# Eth.net
KiCad netlist of a schematic drawn in Altium Designer
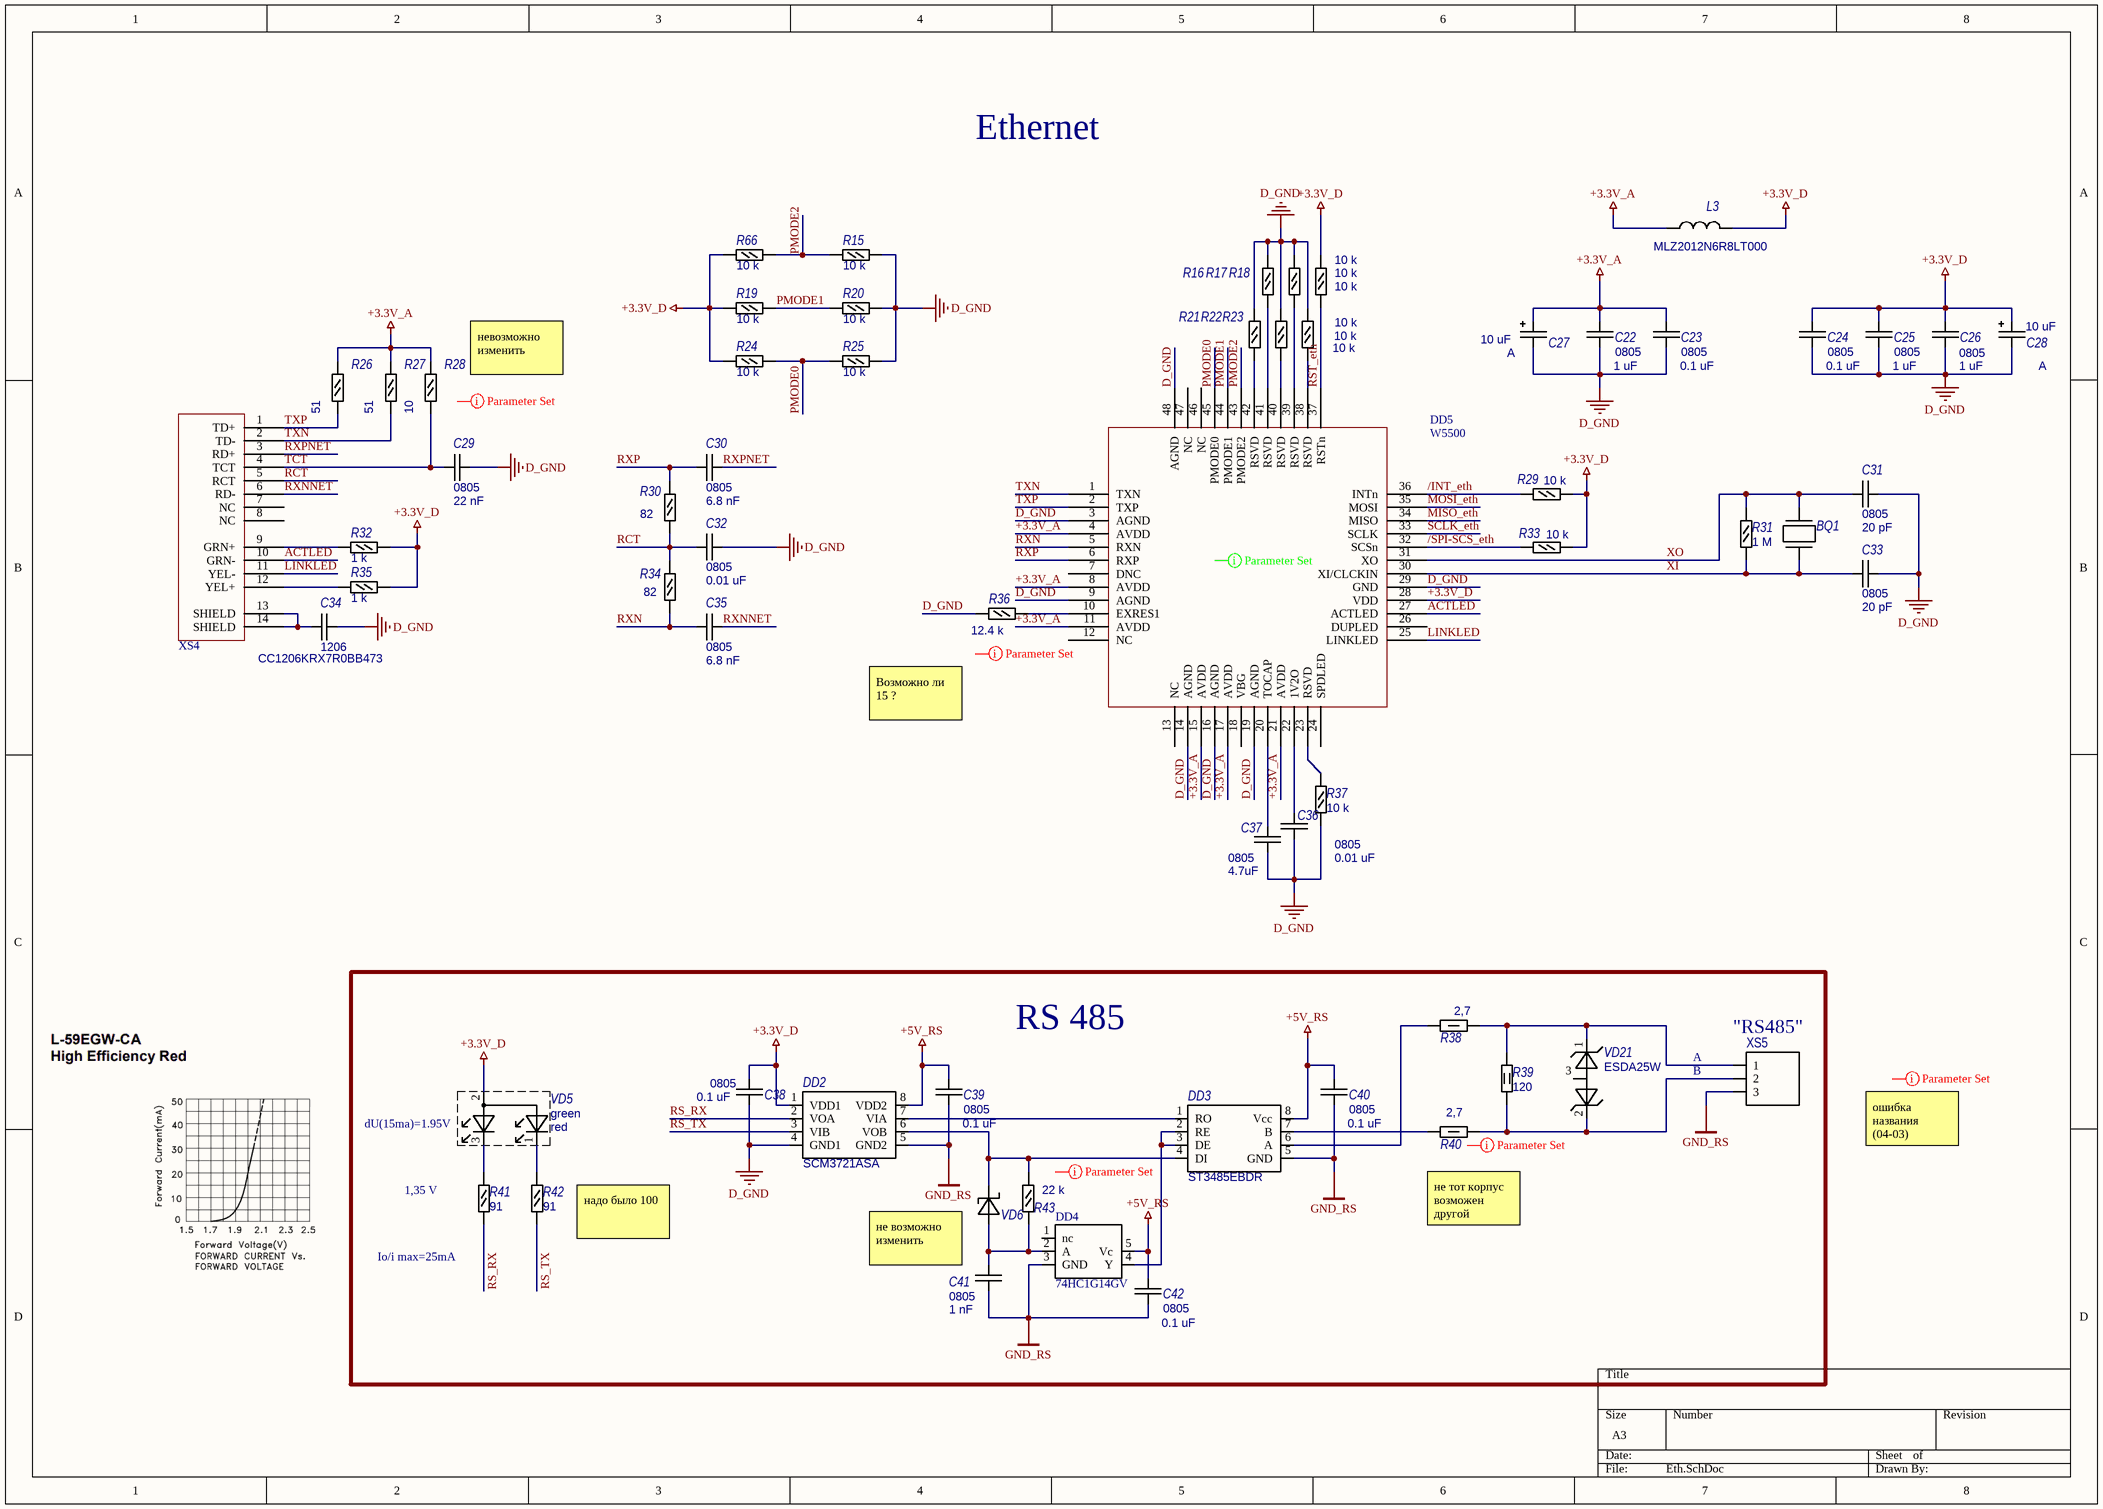
[diagram p0: Eth.SchDoc]

(export (version "E")
  (design (tool "Eeschema 10.0.6"))
  (components
    (comp (ref "BQ1") (value "~") (footprint "Xtal_HC49S") (libsource (lib "Privod_A_K") (part "Xtal")))
    (comp (ref "C22")
      (value "0805")
      (footprint "CAP_0805_(2x1.25x1.3)")
      (description "Керамика")
      (fields (field (name "НОМИНАЛ") "1 uF"))
      (libsource (lib "Privod_A_K") (part "C_0805"))
    )
    (comp (ref "C23")
      (value "0805")
      (footprint "CAP_0805_(2x1.25x1.3)")
      (description "Керамика")
      (fields (field (name "НОМИНАЛ") "0.1 uF"))
      (libsource (lib "Privod_A_K") (part "C_0805"))
    )
    (comp (ref "C24")
      (value "0805")
      (footprint "CAP_0805_(2x1.25x1.3)")
      (description "Керамика")
      (fields (field (name "НОМИНАЛ") "0.1 uF"))
      (libsource (lib "Privod_A_K") (part "C_0805"))
    )
    (comp (ref "C25")
      (value "0805")
      (footprint "CAP_0805_(2x1.25x1.3)")
      (description "Керамика")
      (fields (field (name "НОМИНАЛ") "1 uF"))
      (libsource (lib "Privod_A_K") (part "C_0805"))
    )
    (comp (ref "C26")
      (value "0805")
      (footprint "CAP_0805_(2x1.25x1.3)")
      (description "Керамика")
      (fields (field (name "НОМИНАЛ") "1 uF"))
      (libsource (lib "Privod_A_K") (part "C_0805"))
    )
    (comp (ref "C27")
      (value "TAN_A")
      (footprint "CAP_TAN_A")
      (description "Capacitor")
      (fields (field (name "КОРПУС") "A") (field (name "НОМИНАЛ") "10 uF"))
      (libsource (lib "Privod_A_K") (part "C+_TAN_A"))
    )
    (comp (ref "C28")
      (value "TAN_A")
      (footprint "CAP_TAN_A")
      (description "Capacitor")
      (fields (field (name "КОРПУС") "A") (field (name "НОМИНАЛ") "10 uF"))
      (libsource (lib "Privod_A_K") (part "C+_TAN_A"))
    )
    (comp (ref "C29")
      (value "0805")
      (footprint "CAP_0805_(2x1.25x1.3)")
      (description "Керамика")
      (fields (field (name "НОМИНАЛ") "22 nF"))
      (libsource (lib "Privod_A_K") (part "C_0805"))
    )
    (comp (ref "C30")
      (value "0805")
      (footprint "CAP_0805_(2x1.25x1.3)")
      (description "Керамика")
      (fields (field (name "НОМИНАЛ") "6.8 nF"))
      (libsource (lib "Privod_A_K") (part "C_0805"))
    )
    (comp (ref "C31")
      (value "0805")
      (footprint "CAP_0805_(2x1.25x1.3)")
      (description "Керамика")
      (fields (field (name "НОМИНАЛ") "20 pF"))
      (libsource (lib "Privod_A_K") (part "C_0805"))
    )
    (comp (ref "C32")
      (value "0805")
      (footprint "CAP_0805_(2x1.25x1.3)")
      (description "Керамика")
      (fields (field (name "НОМИНАЛ") "0.01 uF"))
      (libsource (lib "Privod_A_K") (part "C_0805"))
    )
    (comp (ref "C33")
      (value "0805")
      (footprint "CAP_0805_(2x1.25x1.3)")
      (description "Керамика")
      (fields (field (name "НОМИНАЛ") "20 pF"))
      (libsource (lib "Privod_A_K") (part "C_0805"))
    )
    (comp (ref "C34")
      (value "1206")
      (footprint "CAP_1206_(3.2x1.6x1.5)")
      (description "Керамика")
      (fields (field (name "НАИМЕНОВАНИЕ") "CC1206KRX7R0BB473"))
      (libsource (lib "Privod_A_K") (part "C_1206"))
    )
    (comp (ref "C35")
      (value "0805")
      (footprint "CAP_0805_(2x1.25x1.3)")
      (description "Керамика")
      (fields (field (name "НОМИНАЛ") "6.8 nF"))
      (libsource (lib "Privod_A_K") (part "C_0805"))
    )
    (comp (ref "C36")
      (value "0805")
      (footprint "CAP_0805_(2x1.25x1.3)")
      (description "Керамика")
      (fields (field (name "НОМИНАЛ") "0.01 uF"))
      (libsource (lib "Privod_A_K") (part "C_0805"))
    )
    (comp (ref "C37")
      (value "0805")
      (footprint "CAP_0805_(2x1.25x1.3)")
      (description "Керамика")
      (fields (field (name "НОМИНАЛ") "4.7uF"))
      (libsource (lib "Privod_A_K") (part "C_0805"))
    )
    (comp (ref "C38")
      (value "0805")
      (footprint "CAP_0805_(2x1.25x1.3)")
      (description "Керамика")
      (fields (field (name "НОМИНАЛ") "0.1 uF"))
      (libsource (lib "Privod_A_K") (part "C_0805"))
    )
    (comp (ref "C39")
      (value "0805")
      (footprint "CAP_0805_(2x1.25x1.3)")
      (description "Керамика")
      (fields (field (name "НОМИНАЛ") "0.1 uF"))
      (libsource (lib "Privod_A_K") (part "C_0805"))
    )
    (comp (ref "C40")
      (value "0805")
      (footprint "CAP_0805_(2x1.25x1.3)")
      (description "Керамика")
      (fields (field (name "НОМИНАЛ") "0.1 uF"))
      (libsource (lib "Privod_A_K") (part "C_0805"))
    )
    (comp (ref "C41")
      (value "0805")
      (footprint "CAP_0805_(2x1.25x1.3)")
      (description "Керамика")
      (fields (field (name "НОМИНАЛ") "1 nF"))
      (libsource (lib "Privod_A_K") (part "C_0805"))
    )
    (comp (ref "C42")
      (value "0805")
      (footprint "CAP_0805_(2x1.25x1.3)")
      (description "Керамика")
      (fields (field (name "НОМИНАЛ") "0.1 uF"))
      (libsource (lib "Privod_A_K") (part "C_0805"))
    )
    (comp (ref "DD2")
      (value "SCM3721ASA")
      (footprint "SOP-8")
      (description "Dual-ChannelDigital Isolators")
      (libsource (lib "Privod_A_K") (part "DD_SCM3721ASA"))
    )
    (comp (ref "DD3")
      (value "ST3485EBDR")
      (footprint "SO-8_(0.15')")
      (description "RS485/422 Приемопередатчик интерфейса")
      (libsource (lib "Privod_A_K") (part "DD_ST3485EBDR"))
    )
    (comp (ref "DD4")
      (value "74HC1G14GV")
      (footprint "sot-23-5")
      (description "1 канал инвертирующ триггер шмитта")
      (libsource (lib "Privod_A_K") (part "DD_74HC1G14GV"))
    )
    (comp (ref "DD5") (value "W5500") (footprint "LQFP_48") (libsource (lib "Privod_A_K") (part "DD_W5500")))
    (comp (ref "L3")
      (value "PBY201209T-601Y-N")
      (footprint "L_0805")
      (description "L")
      (fields (field (name "НАИМЕНОВАНИЕ") "MLZ2012N6R8LT000"))
      (libsource (lib "Privod_A_K") (part "L_PBY201209T-601Y-N"))
    )
    (comp (ref "R15")
      (value "0805")
      (footprint "RES_0805_(2x1.2x0.45)_0.125Вт")
      (description "Resistor")
      (fields (field (name "НОМИНАЛ") "10 k"))
      (libsource (lib "") (part "R_0805_1"))
    )
    (comp (ref "R16")
      (value "0805")
      (footprint "RES_0805_(2x1.2x0.45)_0.125Вт")
      (description "Resistor")
      (fields (field (name "НОМИНАЛ") "10 k"))
      (libsource (lib "Privod_A_K") (part "R_0805"))
    )
    (comp (ref "R17")
      (value "0805")
      (footprint "RES_0805_(2x1.2x0.45)_0.125Вт")
      (description "Resistor")
      (fields (field (name "НОМИНАЛ") "10 k"))
      (libsource (lib "Privod_A_K") (part "R_0805"))
    )
    (comp (ref "R18")
      (value "0805")
      (footprint "RES_0805_(2x1.2x0.45)_0.125Вт")
      (description "Resistor")
      (fields (field (name "НОМИНАЛ") "10 k"))
      (libsource (lib "Privod_A_K") (part "R_0805"))
    )
    (comp (ref "R19")
      (value "0805")
      (footprint "RES_0805_(2x1.2x0.45)_0.125Вт")
      (description "Resistor")
      (fields (field (name "НОМИНАЛ") "10 k"))
      (libsource (lib "") (part "R_0805_1"))
    )
    (comp (ref "R20")
      (value "0805")
      (footprint "RES_0805_(2x1.2x0.45)_0.125Вт")
      (description "Resistor")
      (fields (field (name "НОМИНАЛ") "10 k"))
      (libsource (lib "") (part "R_0805_1"))
    )
    (comp (ref "R21")
      (value "0805")
      (footprint "RES_0805_(2x1.2x0.45)_0.125Вт")
      (description "Resistor")
      (fields (field (name "НОМИНАЛ") "10 k"))
      (libsource (lib "Privod_A_K") (part "R_0805"))
    )
    (comp (ref "R22")
      (value "0805")
      (footprint "RES_0805_(2x1.2x0.45)_0.125Вт")
      (description "Resistor")
      (fields (field (name "НОМИНАЛ") "10 k"))
      (libsource (lib "Privod_A_K") (part "R_0805"))
    )
    (comp (ref "R23")
      (value "0805")
      (footprint "RES_0805_(2x1.2x0.45)_0.125Вт")
      (description "Resistor")
      (fields (field (name "НОМИНАЛ") "10 k"))
      (libsource (lib "Privod_A_K") (part "R_0805"))
    )
    (comp (ref "R24")
      (value "0805")
      (footprint "RES_0805_(2x1.2x0.45)_0.125Вт")
      (description "Resistor")
      (fields (field (name "НОМИНАЛ") "10 k"))
      (libsource (lib "") (part "R_0805_1"))
    )
    (comp (ref "R25")
      (value "0805")
      (footprint "RES_0805_(2x1.2x0.45)_0.125Вт")
      (description "Resistor")
      (fields (field (name "НОМИНАЛ") "10 k"))
      (libsource (lib "") (part "R_0805_1"))
    )
    (comp (ref "R26")
      (value "0805")
      (footprint "RES_0805_(2x1.2x0.45)_0.125Вт")
      (description "Resistor")
      (fields (field (name "НОМИНАЛ") "51"))
      (libsource (lib "Privod_A_K") (part "R_0805"))
    )
    (comp (ref "R27")
      (value "0805")
      (footprint "RES_0805_(2x1.2x0.45)_0.125Вт")
      (description "Resistor")
      (fields (field (name "НОМИНАЛ") "51"))
      (libsource (lib "Privod_A_K") (part "R_0805"))
    )
    (comp (ref "R28")
      (value "0805")
      (footprint "RES_0805_(2x1.2x0.45)_0.125Вт")
      (description "Resistor")
      (fields (field (name "НОМИНАЛ") "10"))
      (libsource (lib "Privod_A_K") (part "R_0805"))
    )
    (comp (ref "R29")
      (value "0805")
      (footprint "RES_0805_(2x1.2x0.45)_0.125Вт")
      (description "Resistor")
      (fields (field (name "НОМИНАЛ") "10 k"))
      (libsource (lib "") (part "R_0805_1"))
    )
    (comp (ref "R30")
      (value "0805")
      (footprint "RES_0805_(2x1.2x0.45)_0.125Вт")
      (description "Resistor")
      (fields (field (name "НОМИНАЛ") "82"))
      (libsource (lib "Privod_A_K") (part "R_0805"))
    )
    (comp (ref "R31")
      (value "0805")
      (footprint "RES_0805_(2x1.2x0.45)_0.125Вт")
      (description "Resistor")
      (fields (field (name "НОМИНАЛ") "1 M"))
      (libsource (lib "Privod_A_K") (part "R_0805"))
    )
    (comp (ref "R32")
      (value "0805")
      (footprint "RES_0805_(2x1.2x0.45)_0.125Вт")
      (description "Resistor")
      (fields (field (name "НОМИНАЛ") "1 k"))
      (libsource (lib "") (part "R_0805_1"))
    )
    (comp (ref "R33")
      (value "0805")
      (footprint "RES_0805_(2x1.2x0.45)_0.125Вт")
      (description "Resistor")
      (fields (field (name "НОМИНАЛ") "10 k"))
      (libsource (lib "") (part "R_0805_1"))
    )
    (comp (ref "R34")
      (value "0805")
      (footprint "RES_0805_(2x1.2x0.45)_0.125Вт")
      (description "Resistor")
      (fields (field (name "НОМИНАЛ") "82"))
      (libsource (lib "Privod_A_K") (part "R_0805"))
    )
    (comp (ref "R35")
      (value "0805")
      (footprint "RES_0805_(2x1.2x0.45)_0.125Вт")
      (description "Resistor")
      (fields (field (name "НОМИНАЛ") "1 k"))
      (libsource (lib "") (part "R_0805_1"))
    )
    (comp (ref "R36")
      (value "0805")
      (footprint "RES_0805_(2x1.2x0.45)_0.125Вт")
      (description "Resistor")
      (fields (field (name "НОМИНАЛ") "12.4 k"))
      (libsource (lib "") (part "R_0805_1"))
    )
    (comp (ref "R37")
      (value "0805")
      (footprint "RES_0805_(2x1.2x0.45)_0.125Вт")
      (description "Resistor")
      (fields (field (name "НОМИНАЛ") "10 k"))
      (libsource (lib "Privod_A_K") (part "R_0805"))
    )
    (comp (ref "R38")
      (value "1210")
      (footprint "RES_1210_(3.2x2.5x0.55)_0.5Вт")
      (description "Resistor")
      (fields (field (name "НОМИНАЛ") "2,7"))
      (libsource (lib "Privod_A_K") (part "R_1210"))
    )
    (comp (ref "R39")
      (value "2512")
      (footprint "RES_2512_(6.3x3.1x0.6)_2Вт")
      (description "Токочувствительные резисторы – для поверхностного монтажа 2watts 2512")
      (fields (field (name "НОМИНАЛ") "120"))
      (libsource (lib "Privod_A_K") (part "R_2512"))
    )
    (comp (ref "R40")
      (value "1210")
      (footprint "RES_1210_(3.2x2.5x0.55)_0.5Вт")
      (description "Resistor")
      (fields (field (name "НОМИНАЛ") "2,7"))
      (libsource (lib "Privod_A_K") (part "R_1210"))
    )
    (comp (ref "R41")
      (value "0805")
      (footprint "RES_0805_(2x1.2x0.45)_0.125Вт")
      (description "Resistor")
      (fields (field (name "НОМИНАЛ") "91"))
      (libsource (lib "Privod_A_K") (part "R_0805"))
    )
    (comp (ref "R42")
      (value "0805")
      (footprint "RES_0805_(2x1.2x0.45)_0.125Вт")
      (description "Resistor")
      (fields (field (name "НОМИНАЛ") "91"))
      (libsource (lib "Privod_A_K") (part "R_0805"))
    )
    (comp (ref "R43")
      (value "0805")
      (footprint "RES_0805_(2x1.2x0.45)_0.125Вт")
      (description "Resistor")
      (fields (field (name "НОМИНАЛ") "22 k"))
      (libsource (lib "") (part "R_0805_2"))
    )
    (comp (ref "R66")
      (value "0805")
      (footprint "RES_0805_(2x1.2x0.45)_0.125Вт")
      (description "Resistor")
      (fields (field (name "НОМИНАЛ") "10 k"))
      (libsource (lib "") (part "R_0805_1"))
    )
    (comp (ref "VD5")
      (value "VD_Ledx2_dip")
      (footprint "VD_LEDsx2")
      (fields (field (name "ТИП") "green") (field (name "ПРИМЕЧАНИЯ") "red"))
      (libsource (lib "Privod_A_K") (part "VD_Ledx2_dip"))
    )
    (comp (ref "VD6")
      (value "VD_SH_SMA")
      (footprint "VD_SMA_(Do-214AC)")
      (description "Sh_Diode")
      (libsource (lib "Privod_A_K") (part "VD_SH_SMA"))
    )
    (comp (ref "VD21")
      (value "ESDA25W")
      (footprint "SOT-323-3L")
      (description "Защитный биполярный диод")
      (libsource (lib "Privod_A_K") (part "VD_ESDA25W"))
    )
    (comp (ref "XS4")
      (value "XS_HR911105A")
      (footprint "XS_HR911105A(RJ45)")
      (description "RJ45")
      (libsource (lib "Privod_A_K") (part "XS_HR911105A"))
    )
    (comp (ref "XS5")
      (value "XS_3_pin_3.8mm")
      (footprint "XS_3_Pin _3.8mm")
      (libsource (lib "Privod_A_K") (part "XS_3_pin_3.8mm"))
    )
  )
  (nets
    (net (code "1") (name "+3.3V_A") (class "Default")
      (node (ref "C22") (pin "2") (pinfunction "2_2") (pintype "passive"))
      (node (ref "C23") (pin "2") (pinfunction "2_2") (pintype "passive"))
      (node (ref "C27") (pin "1") (pinfunction "1_1") (pintype "passive"))
      (node (ref "DD5") (pin "11") (pinfunction "AVDD_11") (pintype "passive"))
      (node (ref "DD5") (pin "15") (pinfunction "AVDD_15") (pintype "passive"))
      (node (ref "DD5") (pin "17") (pinfunction "AVDD_17") (pintype "passive"))
      (node (ref "DD5") (pin "21") (pinfunction "AVDD_21") (pintype "passive"))
      (node (ref "DD5") (pin "4") (pinfunction "AVDD_4") (pintype "passive"))
      (node (ref "DD5") (pin "8") (pinfunction "AVDD_8") (pintype "passive"))
      (node (ref "L3") (pin "1") (pinfunction "1_1") (pintype "passive"))
      (node (ref "R26") (pin "2") (pinfunction "2_2") (pintype "passive"))
      (node (ref "R27") (pin "2") (pinfunction "2_2") (pintype "passive"))
      (node (ref "R28") (pin "2") (pinfunction "2_2") (pintype "passive"))
    )
    (net (code "2") (name "+3.3V_D") (class "Default")
      (node (ref "C24") (pin "2") (pinfunction "2_2") (pintype "passive"))
      (node (ref "C25") (pin "2") (pinfunction "2_2") (pintype "passive"))
      (node (ref "C26") (pin "2") (pinfunction "2_2") (pintype "passive"))
      (node (ref "C28") (pin "1") (pinfunction "1_1") (pintype "passive"))
      (node (ref "C38") (pin "2") (pinfunction "2_2") (pintype "passive"))
      (node (ref "DD2") (pin "1") (pinfunction "VDD1_1") (pintype "passive"))
      (node (ref "DD5") (pin "28") (pinfunction "VDD_28") (pintype "passive"))
      (node (ref "L3") (pin "2") (pinfunction "2_2") (pintype "passive"))
      (node (ref "R18") (pin "2") (pinfunction "2_2") (pintype "passive"))
      (node (ref "R19") (pin "1") (pinfunction "1_1") (pintype "passive"))
      (node (ref "R24") (pin "1") (pinfunction "1_1") (pintype "passive"))
      (node (ref "R29") (pin "2") (pinfunction "2_2") (pintype "passive"))
      (node (ref "R32") (pin "2") (pinfunction "2_2") (pintype "passive"))
      (node (ref "R33") (pin "2") (pinfunction "2_2") (pintype "passive"))
      (node (ref "R35") (pin "2") (pinfunction "2_2") (pintype "passive"))
      (node (ref "R66") (pin "1") (pinfunction "1_1") (pintype "passive"))
      (node (ref "VD5") (pin "2") (pinfunction "A_2") (pintype "passive"))
    )
    (net (code "3") (name "+5V_RS") (class "Default")
      (node (ref "C39") (pin "2") (pinfunction "2_2") (pintype "passive"))
      (node (ref "C40") (pin "2") (pinfunction "2_2") (pintype "passive"))
      (node (ref "C42") (pin "2") (pinfunction "2_2") (pintype "passive"))
      (node (ref "DD2") (pin "8") (pinfunction "VDD2_8") (pintype "passive"))
      (node (ref "DD3") (pin "8") (pinfunction "Vcc_8") (pintype "passive"))
      (node (ref "DD4") (pin "5") (pinfunction "Vc_5") (pintype "passive"))
    )
    (net (code "4") (name "/ACTLED") (class "Default")
      (node (ref "DD5") (pin "27") (pinfunction "ACTLED_27") (pintype "passive"))
      (node (ref "XS4") (pin "10") (pinfunction "GRN-_10") (pintype "passive"))
    )
    (net (code "5") (name "/LINKLED") (class "Default")
      (node (ref "DD5") (pin "25") (pinfunction "LINKLED_25") (pintype "passive"))
      (node (ref "XS4") (pin "11") (pinfunction "YEL-_11") (pintype "passive"))
    )
    (net (code "6") (name "/MISO_eth") (class "Default")
      (node (ref "DD5") (pin "34") (pinfunction "MISO_34") (pintype "passive"))
    )
    (net (code "7") (name "/MOSI_eth") (class "Default")
      (node (ref "DD5") (pin "35") (pinfunction "MOSI_35") (pintype "passive"))
    )
    (net (code "8") (name "/PMODE0") (class "Default")
      (node (ref "DD5") (pin "45") (pinfunction "PMODE0_45") (pintype "passive"))
      (node (ref "R24") (pin "2") (pinfunction "2_2") (pintype "passive"))
      (node (ref "R25") (pin "1") (pinfunction "1_1") (pintype "passive"))
    )
    (net (code "9") (name "/PMODE1") (class "Default")
      (node (ref "DD5") (pin "44") (pinfunction "PMODE1_44") (pintype "passive"))
      (node (ref "R19") (pin "2") (pinfunction "2_2") (pintype "passive"))
      (node (ref "R20") (pin "1") (pinfunction "1_1") (pintype "passive"))
    )
    (net (code "10") (name "/PMODE2") (class "Default")
      (node (ref "DD5") (pin "43") (pinfunction "PMODE2_43") (pintype "passive"))
      (node (ref "R15") (pin "1") (pinfunction "1_1") (pintype "passive"))
      (node (ref "R66") (pin "2") (pinfunction "2_2") (pintype "passive"))
    )
    (net (code "11") (name "/RCT") (class "Default")
      (node (ref "C32") (pin "2") (pinfunction "2_2") (pintype "passive"))
      (node (ref "R30") (pin "1") (pinfunction "1_1") (pintype "passive"))
      (node (ref "R34") (pin "2") (pinfunction "2_2") (pintype "passive"))
      (node (ref "XS4") (pin "5") (pinfunction "RCT_5") (pintype "passive"))
    )
    (net (code "12") (name "/RST_eth") (class "Default")
      (node (ref "DD5") (pin "37") (pinfunction "RSTn_37") (pintype "passive"))
      (node (ref "R18") (pin "1") (pinfunction "1_1") (pintype "passive"))
    )
    (net (code "13") (name "/RS_RX") (class "Default")
      (node (ref "DD2") (pin "2") (pinfunction "VOA_2") (pintype "passive"))
      (node (ref "R41") (pin "1") (pinfunction "1_1") (pintype "passive"))
    )
    (net (code "14") (name "/RS_TX") (class "Default")
      (node (ref "DD2") (pin "3") (pinfunction "VIB_3") (pintype "passive"))
      (node (ref "R42") (pin "1") (pinfunction "1_1") (pintype "passive"))
    )
    (net (code "15") (name "/RXN") (class "Default")
      (node (ref "C35") (pin "2") (pinfunction "2_2") (pintype "passive"))
      (node (ref "DD5") (pin "5") (pinfunction "RXN_5") (pintype "passive"))
      (node (ref "R34") (pin "1") (pinfunction "1_1") (pintype "passive"))
    )
    (net (code "16") (name "/RXNNET") (class "Default")
      (node (ref "C35") (pin "1") (pinfunction "1_1") (pintype "passive"))
      (node (ref "XS4") (pin "6") (pinfunction "RD-_6") (pintype "passive"))
    )
    (net (code "17") (name "/RXP") (class "Default")
      (node (ref "C30") (pin "2") (pinfunction "2_2") (pintype "passive"))
      (node (ref "DD5") (pin "6") (pinfunction "RXP_6") (pintype "passive"))
      (node (ref "R30") (pin "2") (pinfunction "2_2") (pintype "passive"))
    )
    (net (code "18") (name "/RXPNET") (class "Default")
      (node (ref "C30") (pin "1") (pinfunction "1_1") (pintype "passive"))
      (node (ref "XS4") (pin "3") (pinfunction "RD+_3") (pintype "passive"))
    )
    (net (code "19") (name "/SCLK_eth") (class "Default")
      (node (ref "DD5") (pin "33") (pinfunction "SCLK_33") (pintype "passive"))
    )
    (net (code "20") (name "/TCT") (class "Default")
      (node (ref "C29") (pin "2") (pinfunction "2_2") (pintype "passive"))
      (node (ref "R28") (pin "1") (pinfunction "1_1") (pintype "passive"))
      (node (ref "XS4") (pin "4") (pinfunction "TCT_4") (pintype "passive"))
    )
    (net (code "21") (name "/TXN") (class "Default")
      (node (ref "DD5") (pin "1") (pinfunction "TXN_1") (pintype "passive"))
      (node (ref "R27") (pin "1") (pinfunction "1_1") (pintype "passive"))
      (node (ref "XS4") (pin "2") (pinfunction "TD-_2") (pintype "passive"))
    )
    (net (code "22") (name "/TXP") (class "Default")
      (node (ref "DD5") (pin "2") (pinfunction "TXP_2") (pintype "passive"))
      (node (ref "R26") (pin "1") (pinfunction "1_1") (pintype "passive"))
      (node (ref "XS4") (pin "1") (pinfunction "TD+_1") (pintype "passive"))
    )
    (net (code "23") (name "/XI") (class "Default")
      (node (ref "BQ1") (pin "1") (pinfunction "1_1") (pintype "passive"))
      (node (ref "C33") (pin "2") (pinfunction "2_2") (pintype "passive"))
      (node (ref "DD5") (pin "30") (pinfunction "XI/CLCKIN_30") (pintype "passive"))
      (node (ref "R31") (pin "1") (pinfunction "1_1") (pintype "passive"))
    )
    (net (code "24") (name "/XO") (class "Default")
      (node (ref "BQ1") (pin "2") (pinfunction "2_2") (pintype "passive"))
      (node (ref "C31") (pin "2") (pinfunction "2_2") (pintype "passive"))
      (node (ref "DD5") (pin "31") (pinfunction "XO_31") (pintype "passive"))
      (node (ref "R31") (pin "2") (pinfunction "2_2") (pintype "passive"))
    )
    (net (code "25") (name "/{slash}INT_eth") (class "Default")
      (node (ref "DD5") (pin "36") (pinfunction "INTn_36") (pintype "passive"))
      (node (ref "R29") (pin "1") (pinfunction "1_1") (pintype "passive"))
    )
    (net (code "26") (name "/{slash}SPI-SCS_eth") (class "Default")
      (node (ref "DD5") (pin "32") (pinfunction "SCSn_32") (pintype "passive"))
      (node (ref "R33") (pin "1") (pinfunction "1_1") (pintype "passive"))
    )
    (net (code "27") (name "D_GND") (class "Default")
      (node (ref "C22") (pin "1") (pinfunction "1_1") (pintype "passive"))
      (node (ref "C23") (pin "1") (pinfunction "1_1") (pintype "passive"))
      (node (ref "C24") (pin "1") (pinfunction "1_1") (pintype "passive"))
      (node (ref "C25") (pin "1") (pinfunction "1_1") (pintype "passive"))
      (node (ref "C26") (pin "1") (pinfunction "1_1") (pintype "passive"))
      (node (ref "C27") (pin "2") (pinfunction "2_2") (pintype "passive"))
      (node (ref "C28") (pin "2") (pinfunction "2_2") (pintype "passive"))
      (node (ref "C29") (pin "1") (pinfunction "1_1") (pintype "passive"))
      (node (ref "C31") (pin "1") (pinfunction "1_1") (pintype "passive"))
      (node (ref "C32") (pin "1") (pinfunction "1_1") (pintype "passive"))
      (node (ref "C33") (pin "1") (pinfunction "1_1") (pintype "passive"))
      (node (ref "C34") (pin "2") (pinfunction "2_2") (pintype "passive"))
      (node (ref "C36") (pin "1") (pinfunction "1_1") (pintype "passive"))
      (node (ref "C37") (pin "1") (pinfunction "1_1") (pintype "passive"))
      (node (ref "C38") (pin "1") (pinfunction "1_1") (pintype "passive"))
      (node (ref "DD2") (pin "4") (pinfunction "GND1_4") (pintype "passive"))
      (node (ref "DD5") (pin "14") (pinfunction "AGND_14") (pintype "passive"))
      (node (ref "DD5") (pin "16") (pinfunction "AGND_16") (pintype "passive"))
      (node (ref "DD5") (pin "19") (pinfunction "AGND_19") (pintype "passive"))
      (node (ref "DD5") (pin "29") (pinfunction "GND_29") (pintype "passive"))
      (node (ref "DD5") (pin "3") (pinfunction "AGND_3") (pintype "passive"))
      (node (ref "DD5") (pin "48") (pinfunction "AGND_48") (pintype "passive"))
      (node (ref "DD5") (pin "9") (pinfunction "AGND_9") (pintype "passive"))
      (node (ref "R15") (pin "2") (pinfunction "2_2") (pintype "passive"))
      (node (ref "R16") (pin "2") (pinfunction "2_2") (pintype "passive"))
      (node (ref "R17") (pin "2") (pinfunction "2_2") (pintype "passive"))
      (node (ref "R20") (pin "2") (pinfunction "2_2") (pintype "passive"))
      (node (ref "R21") (pin "2") (pinfunction "2_2") (pintype "passive"))
      (node (ref "R22") (pin "2") (pinfunction "2_2") (pintype "passive"))
      (node (ref "R23") (pin "2") (pinfunction "2_2") (pintype "passive"))
      (node (ref "R25") (pin "2") (pinfunction "2_2") (pintype "passive"))
      (node (ref "R36") (pin "1") (pinfunction "1_1") (pintype "passive"))
      (node (ref "R37") (pin "1") (pinfunction "1_1") (pintype "passive"))
    )
    (net (code "28") (name "GND_RS") (class "Default")
      (node (ref "C39") (pin "1") (pinfunction "1_1") (pintype "passive"))
      (node (ref "C40") (pin "1") (pinfunction "1_1") (pintype "passive"))
      (node (ref "C41") (pin "1") (pinfunction "1_1") (pintype "passive"))
      (node (ref "C42") (pin "1") (pinfunction "1_1") (pintype "passive"))
      (node (ref "DD2") (pin "5") (pinfunction "GND2_5") (pintype "passive"))
      (node (ref "DD3") (pin "5") (pinfunction "GND_5") (pintype "passive"))
      (node (ref "DD4") (pin "3") (pinfunction "GND_3") (pintype "passive"))
      (node (ref "XS5") (pin "3") (pinfunction "3_3") (pintype "passive"))
    )
    (net (code "29") (name "Net-(C34-Pad1)") (class "Default")
      (node (ref "C34") (pin "1") (pinfunction "1_1") (pintype "passive"))
      (node (ref "XS4") (pin "13") (pinfunction "SHIELD_13") (pintype "passive"))
      (node (ref "XS4") (pin "14") (pinfunction "SHIELD_14") (pintype "passive"))
    )
    (net (code "30") (name "Net-(DD2-VIA)") (class "Default")
      (node (ref "DD2") (pin "7") (pinfunction "VIA_7") (pintype "passive"))
      (node (ref "DD3") (pin "1") (pinfunction "RO_1") (pintype "passive"))
    )
    (net (code "31") (name "Net-(DD2-VOB)") (class "Default")
      (node (ref "DD2") (pin "6") (pinfunction "VOB_6") (pintype "passive"))
      (node (ref "DD3") (pin "4") (pinfunction "DI_4") (pintype "passive"))
      (node (ref "R43") (pin "1") (pinfunction "1_1") (pintype "passive"))
      (node (ref "VD6") (pin "2") (pinfunction "K_2") (pintype "passive"))
    )
    (net (code "32") (name "Net-(DD3-A)") (class "Default")
      (node (ref "DD3") (pin "6") (pinfunction "A_6") (pintype "passive"))
      (node (ref "R38") (pin "1") (pinfunction "1_1") (pintype "passive"))
    )
    (net (code "33") (name "Net-(DD3-B)") (class "Default")
      (node (ref "DD3") (pin "7") (pinfunction "B_7") (pintype "passive"))
      (node (ref "R40") (pin "1") (pinfunction "1_1") (pintype "passive"))
    )
    (net (code "34") (name "Net-(DD3-DE)") (class "Default")
      (node (ref "DD3") (pin "2") (pinfunction "RE_2") (pintype "passive"))
      (node (ref "DD3") (pin "3") (pinfunction "DE_3") (pintype "passive"))
      (node (ref "DD4") (pin "4") (pinfunction "Y_4") (pintype "passive"))
    )
    (net (code "35") (name "Net-(DD4-A)") (class "Default")
      (node (ref "C41") (pin "2") (pinfunction "2_2") (pintype "passive"))
      (node (ref "DD4") (pin "2") (pinfunction "A_2") (pintype "passive"))
      (node (ref "R43") (pin "2") (pinfunction "2_2") (pintype "passive"))
      (node (ref "VD6") (pin "1") (pinfunction "A_1") (pintype "passive"))
    )
    (net (code "36") (name "Net-(DD5-1V2O)") (class "Default")
      (node (ref "C36") (pin "2") (pinfunction "2_2") (pintype "passive"))
      (node (ref "DD5") (pin "22") (pinfunction "1V2O_22") (pintype "passive"))
    )
    (net (code "37") (name "Net-(DD5-EXRES1)") (class "Default")
      (node (ref "DD5") (pin "10") (pinfunction "EXRES1_10") (pintype "passive"))
      (node (ref "R36") (pin "2") (pinfunction "2_2") (pintype "passive"))
    )
    (net (code "38") (name "Net-(DD5-RSVD-Pad23)") (class "Default")
      (node (ref "DD5") (pin "23") (pinfunction "RSVD_23") (pintype "passive"))
      (node (ref "R37") (pin "2") (pinfunction "2_2") (pintype "passive"))
    )
    (net (code "39") (name "Net-(DD5-RSVD-Pad38)") (class "Default")
      (node (ref "DD5") (pin "38") (pinfunction "RSVD_38") (pintype "passive"))
      (node (ref "R23") (pin "1") (pinfunction "1_1") (pintype "passive"))
    )
    (net (code "40") (name "Net-(DD5-RSVD-Pad39)") (class "Default")
      (node (ref "DD5") (pin "39") (pinfunction "RSVD_39") (pintype "passive"))
      (node (ref "R17") (pin "1") (pinfunction "1_1") (pintype "passive"))
    )
    (net (code "41") (name "Net-(DD5-RSVD-Pad40)") (class "Default")
      (node (ref "DD5") (pin "40") (pinfunction "RSVD_40") (pintype "passive"))
      (node (ref "R22") (pin "1") (pinfunction "1_1") (pintype "passive"))
    )
    (net (code "42") (name "Net-(DD5-RSVD-Pad41)") (class "Default")
      (node (ref "DD5") (pin "41") (pinfunction "RSVD_41") (pintype "passive"))
      (node (ref "R16") (pin "1") (pinfunction "1_1") (pintype "passive"))
    )
    (net (code "43") (name "Net-(DD5-RSVD-Pad42)") (class "Default")
      (node (ref "DD5") (pin "42") (pinfunction "RSVD_42") (pintype "passive"))
      (node (ref "R21") (pin "1") (pinfunction "1_1") (pintype "passive"))
    )
    (net (code "44") (name "Net-(DD5-TOCAP)") (class "Default")
      (node (ref "C37") (pin "2") (pinfunction "2_2") (pintype "passive"))
      (node (ref "DD5") (pin "20") (pinfunction "TOCAP_20") (pintype "passive"))
    )
    (net (code "45") (name "Net-(R38-Pad2)") (class "Default")
      (node (ref "R38") (pin "2") (pinfunction "2_2") (pintype "passive"))
      (node (ref "R39") (pin "2") (pinfunction "2_2") (pintype "passive"))
      (node (ref "VD21") (pin "1") (pinfunction "1_1") (pintype "passive"))
      (node (ref "XS5") (pin "1") (pinfunction "1_1") (pintype "passive"))
    )
    (net (code "46") (name "Net-(R39-Pad1)") (class "Default")
      (node (ref "R39") (pin "1") (pinfunction "1_1") (pintype "passive"))
      (node (ref "R40") (pin "2") (pinfunction "2_2") (pintype "passive"))
      (node (ref "VD21") (pin "2") (pinfunction "2_2") (pintype "passive"))
      (node (ref "XS5") (pin "2") (pinfunction "2_2") (pintype "passive"))
    )
    (net (code "47") (name "Net-(VD5-K1)") (class "Default")
      (node (ref "R42") (pin "2") (pinfunction "2_2") (pintype "passive"))
      (node (ref "VD5") (pin "1") (pinfunction "K1_1") (pintype "passive"))
    )
    (net (code "48") (name "Net-(VD5-K2)") (class "Default")
      (node (ref "R41") (pin "2") (pinfunction "2_2") (pintype "passive"))
      (node (ref "VD5") (pin "3") (pinfunction "K2_3") (pintype "passive"))
    )
    (net (code "49") (name "Net-(XS4-GRN+)") (class "Default")
      (node (ref "R32") (pin "1") (pinfunction "1_1") (pintype "passive"))
      (node (ref "XS4") (pin "9") (pinfunction "GRN+_9") (pintype "passive"))
    )
    (net (code "50") (name "Net-(XS4-YEL+)") (class "Default")
      (node (ref "R35") (pin "1") (pinfunction "1_1") (pintype "passive"))
      (node (ref "XS4") (pin "12") (pinfunction "YEL+_12") (pintype "passive"))
    )
    (net (code "51") (name "unconnected-(DD4-nc-Pad1)") (class "Default")
      (node (ref "DD4") (pin "1") (pinfunction "nc_1") (pintype "passive"))
    )
    (net (code "52") (name "unconnected-(DD5-DNC-Pad7)") (class "Default")
      (node (ref "DD5") (pin "7") (pinfunction "DNC_7") (pintype "passive"))
    )
    (net (code "53") (name "unconnected-(DD5-DUPLED-Pad26)") (class "Default")
      (node (ref "DD5") (pin "26") (pinfunction "DUPLED_26") (pintype "passive"))
    )
    (net (code "54") (name "unconnected-(DD5-NC-Pad12)") (class "Default")
      (node (ref "DD5") (pin "12") (pinfunction "NC_12") (pintype "passive"))
    )
    (net (code "55") (name "unconnected-(DD5-NC-Pad13)") (class "Default")
      (node (ref "DD5") (pin "13") (pinfunction "NC_13") (pintype "passive"))
    )
    (net (code "56") (name "unconnected-(DD5-NC-Pad46)") (class "Default")
      (node (ref "DD5") (pin "46") (pinfunction "NC_46") (pintype "passive"))
    )
    (net (code "57") (name "unconnected-(DD5-NC-Pad47)") (class "Default")
      (node (ref "DD5") (pin "47") (pinfunction "NC_47") (pintype "passive"))
    )
    (net (code "58") (name "unconnected-(DD5-SPDLED-Pad24)") (class "Default")
      (node (ref "DD5") (pin "24") (pinfunction "SPDLED_24") (pintype "passive"))
    )
    (net (code "59") (name "unconnected-(DD5-VBG-Pad18)") (class "Default")
      (node (ref "DD5") (pin "18") (pinfunction "VBG_18") (pintype "passive"))
    )
    (net (code "60") (name "unconnected-(VD21-Pad3)") (class "Default")
      (node (ref "VD21") (pin "3") (pinfunction "3_3") (pintype "passive"))
    )
    (net (code "61") (name "unconnected-(XS4-NC-Pad7)") (class "Default")
      (node (ref "XS4") (pin "7") (pinfunction "NC_7") (pintype "passive"))
    )
    (net (code "62") (name "unconnected-(XS4-NC-Pad8)") (class "Default")
      (node (ref "XS4") (pin "8") (pinfunction "NC_8") (pintype "passive"))
    )
  )
)
